# ADC.net
KiCad netlist of a schematic drawn in Altium Designer
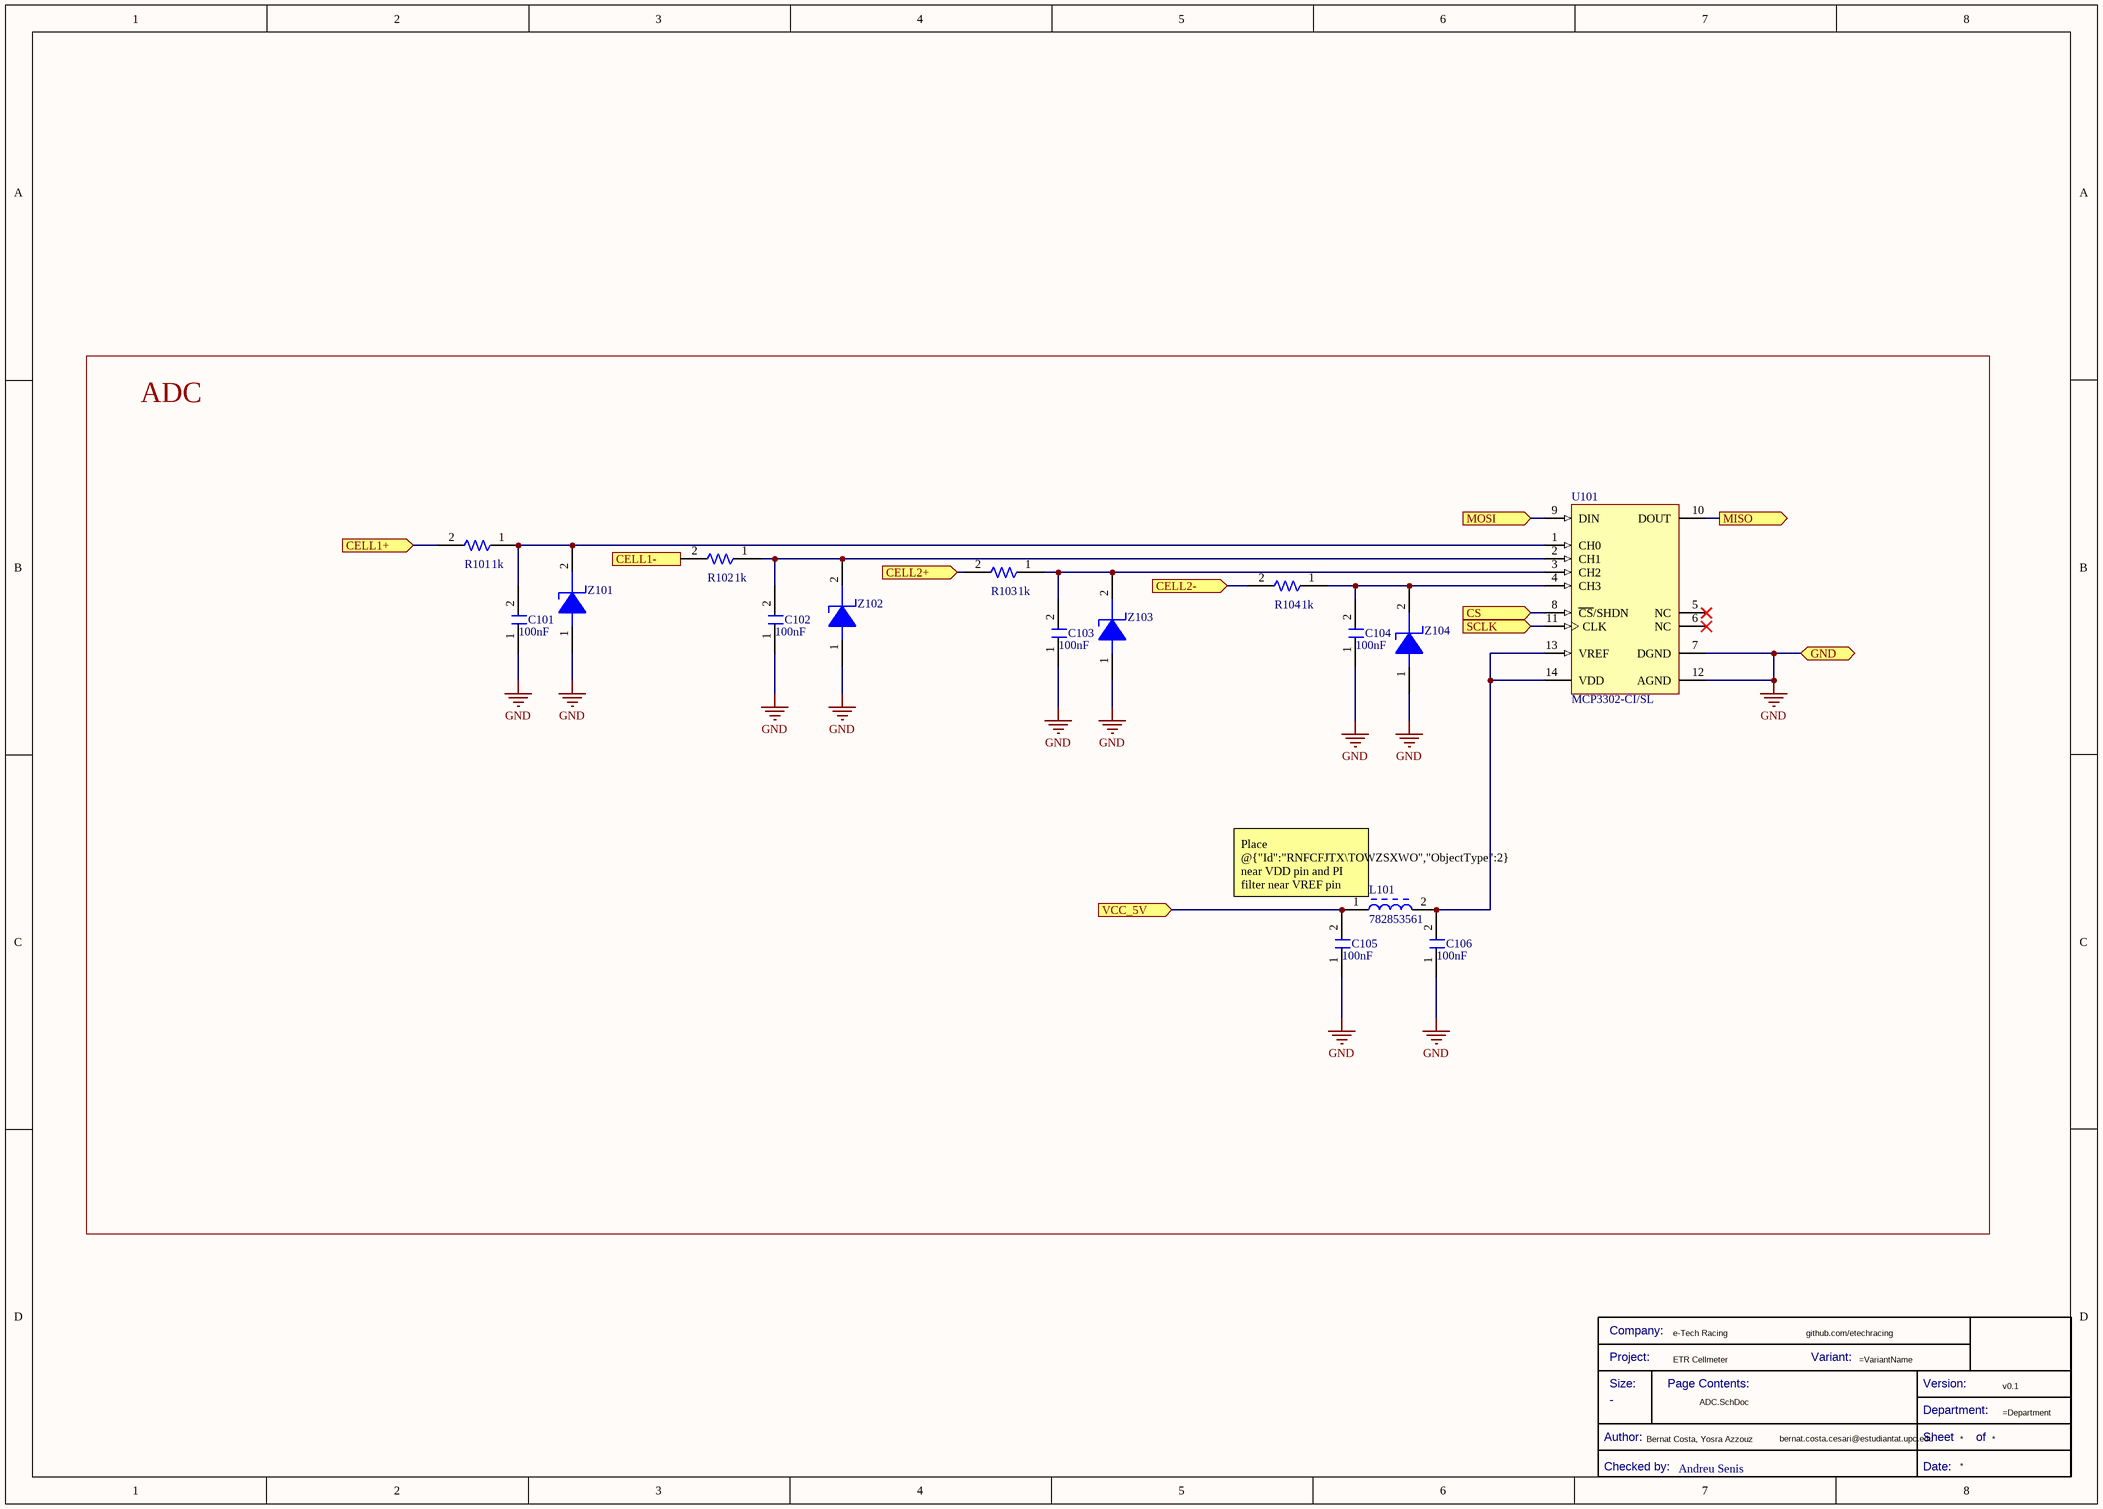
[diagram p0: ADC.SchDoc]

(export (version "E")
  (design (tool "Eeschema 10.0.6"))
  (components
    (comp (ref "C101")
      (value "100nF")
      (footprint "C0805FNPC-R")
      (description "Cap, 0.1ΜF, 50V, 10%, X7R, 0805")
      (fields
        (field (name "TOLERANCE") "10%")
        (field (name "Comment") "C100n-50V-0805FNPC-X7R")
        (field (name ".CREATOR") "DR")
      )
      (libsource (lib "EMEA- E-Tech Racing- I'Escola d'Enginyeria de Barcelona Est") (part "C100p-50V-0805FNPC-C0G/NP0"))
    )
    (comp (ref "C102")
      (value "100nF")
      (footprint "C0805FNPC-R")
      (description "Cap, 0.1ΜF, 50V, 10%, X7R, 0805")
      (fields
        (field (name "TOLERANCE") "10%")
        (field (name "Comment") "C100n-50V-0805FNPC-X7R")
        (field (name ".CREATOR") "DR")
      )
      (libsource (lib "EMEA- E-Tech Racing- I'Escola d'Enginyeria de Barcelona Est") (part "C100p-50V-0805FNPC-C0G/NP0"))
    )
    (comp (ref "C103")
      (value "100nF")
      (footprint "C0805FNPC-R")
      (description "Cap, 0.1ΜF, 50V, 10%, X7R, 0805")
      (fields
        (field (name "TOLERANCE") "10%")
        (field (name "Comment") "C100n-50V-0805FNPC-X7R")
        (field (name ".CREATOR") "DR")
      )
      (libsource (lib "EMEA- E-Tech Racing- I'Escola d'Enginyeria de Barcelona Est") (part "C100p-50V-0805FNPC-C0G/NP0"))
    )
    (comp (ref "C104")
      (value "100nF")
      (footprint "C0805FNPC-R")
      (description "Cap, 0.1ΜF, 50V, 10%, X7R, 0805")
      (fields
        (field (name "TOLERANCE") "10%")
        (field (name "Comment") "C100n-50V-0805FNPC-X7R")
        (field (name ".CREATOR") "DR")
      )
      (libsource (lib "EMEA- E-Tech Racing- I'Escola d'Enginyeria de Barcelona Est") (part "C100p-50V-0805FNPC-C0G/NP0"))
    )
    (comp (ref "C105")
      (value "100nF")
      (footprint "C0805FNPC-R")
      (description "Cap, 0.1ΜF, 50V, 10%, X7R, 0805")
      (fields
        (field (name "TOLERANCE") "10%")
        (field (name "Comment") "C100n-50V-0805FNPC-X7R")
        (field (name ".CREATOR") "DR")
      )
      (libsource (lib "EMEA- E-Tech Racing- I'Escola d'Enginyeria de Barcelona Est") (part "C100p-50V-0805FNPC-C0G/NP0"))
    )
    (comp (ref "C106")
      (value "100nF")
      (footprint "C0805FNPC-R")
      (description "Cap, 0.1ΜF, 50V, 10%, X7R, 0805")
      (fields
        (field (name "TOLERANCE") "10%")
        (field (name "Comment") "C100n-50V-0805FNPC-X7R")
        (field (name ".CREATOR") "DR")
      )
      (libsource (lib "EMEA- E-Tech Racing- I'Escola d'Enginyeria de Barcelona Est") (part "C100p-50V-0805FNPC-C0G/NP0"))
    )
    (comp (ref "L101")
      (value "782853561")
      (footprint "L_Ferrite_bead_0805")
      (fields
        (field (name "TOLERANCE") "25%")
        (field (name "MANUFACTURER PART NUMBER") "BLM18EG331TN1D")
        (field (name "MANUFACTURER") "Murata")
        (field (name ".CREATOR") "GP")
      )
      (libsource (lib "EMEA- E-Tech Racing- I'Escola d'Enginyeria de Barcelona Est") (part "L_Ferrite_bead_782853561"))
    )
    (comp (ref "R101")
      (value "1k")
      (footprint "0805")
      (description "Fixed Resistor, Thin Film, 0.125W, 1000ohm, 150V, 0.1% +/-Tol, 15ppm/Cel, Surface Mount, 0805")
      (fields (field (name "POWER") "125mW") (field (name "TOLERANCE") "0.1%"))
      (libsource (lib "EMEA- E-Tech Racing- I'Escola d'Enginyeria de Barcelona Est") (part "R9.09K-1206FTK"))
    )
    (comp (ref "R102")
      (value "1k")
      (footprint "0805")
      (description "Fixed Resistor, Thin Film, 0.125W, 1000ohm, 150V, 0.1% +/-Tol, 15ppm/Cel, Surface Mount, 0805")
      (fields (field (name "POWER") "125mW") (field (name "TOLERANCE") "0.1%"))
      (libsource (lib "EMEA- E-Tech Racing- I'Escola d'Enginyeria de Barcelona Est") (part "R9.09K-1206FTK"))
    )
    (comp (ref "R103")
      (value "1k")
      (footprint "0805")
      (description "Fixed Resistor, Thin Film, 0.125W, 1000ohm, 150V, 0.1% +/-Tol, 15ppm/Cel, Surface Mount, 0805")
      (fields (field (name "POWER") "125mW") (field (name "TOLERANCE") "0.1%"))
      (libsource (lib "EMEA- E-Tech Racing- I'Escola d'Enginyeria de Barcelona Est") (part "R9.09K-1206FTK"))
    )
    (comp (ref "R104")
      (value "1k")
      (footprint "0805")
      (description "Fixed Resistor, Thin Film, 0.125W, 1000ohm, 150V, 0.1% +/-Tol, 15ppm/Cel, Surface Mount, 0805")
      (fields (field (name "POWER") "125mW") (field (name "TOLERANCE") "0.1%"))
      (libsource (lib "EMEA- E-Tech Racing- I'Escola d'Enginyeria de Barcelona Est") (part "R9.09K-1206FTK"))
    )
    (comp (ref "U101")
      (value "MCP3302-CI/SL")
      (footprint "SOIC-SL14_L")
      (description "ADC, Successive Approximation, 13-Bit, 1 Func, 4 Channel, Serial Access, PDSO14")
      (libsource (lib "EMEA- E-Tech Racing- I'Escola d'Enginyeria de Barcelona Est") (part "CON-ADC-MCP3004-14"))
    )
    (comp (ref "Z101")
      (value "BZD27B5V1P-M3-08")
      (footprint "SODFL370X108-2N")
      (description "Zener Diode, 5.1V V(Z), 2%, 0.8W, Silicon, Unidirectional, DO-219AB")
      (libsource (lib "EMEA- E-Tech Racing- I'Escola d'Enginyeria de Barcelona Est") (part "BZD27B5V1P-M3-08-Symbol-1"))
    )
    (comp (ref "Z102")
      (value "BZD27B5V1P-M3-08")
      (footprint "SODFL370X108-2N")
      (description "Zener Diode, 5.1V V(Z), 2%, 0.8W, Silicon, Unidirectional, DO-219AB")
      (libsource (lib "EMEA- E-Tech Racing- I'Escola d'Enginyeria de Barcelona Est") (part "BZD27B5V1P-M3-08-Symbol-1"))
    )
    (comp (ref "Z103")
      (value "BZD27B5V1P-M3-08")
      (footprint "SODFL370X108-2N")
      (description "Zener Diode, 5.1V V(Z), 2%, 0.8W, Silicon, Unidirectional, DO-219AB")
      (libsource (lib "EMEA- E-Tech Racing- I'Escola d'Enginyeria de Barcelona Est") (part "BZD27B5V1P-M3-08-Symbol-1"))
    )
    (comp (ref "Z104")
      (value "BZD27B5V1P-M3-08")
      (footprint "SODFL370X108-2N")
      (description "Zener Diode, 5.1V V(Z), 2%, 0.8W, Silicon, Unidirectional, DO-219AB")
      (libsource (lib "EMEA- E-Tech Racing- I'Escola d'Enginyeria de Barcelona Est") (part "BZD27B5V1P-M3-08-Symbol-1"))
    )
  )
  (nets
    (net (code "1") (name "/CELL1+") (class "Default")
      (node (ref "R101") (pin "2") (pinfunction "2_2") (pintype "passive"))
    )
    (net (code "2") (name "/CELL1-") (class "Default")
      (node (ref "R102") (pin "2") (pinfunction "2_2") (pintype "passive"))
    )
    (net (code "3") (name "/CELL2+") (class "Default")
      (node (ref "R103") (pin "2") (pinfunction "2_2") (pintype "passive"))
    )
    (net (code "4") (name "/CELL2-") (class "Default")
      (node (ref "R104") (pin "2") (pinfunction "2_2") (pintype "passive"))
    )
    (net (code "5") (name "/CS") (class "Default")
      (node (ref "U101") (pin "8") (pinfunction "~{CS}/SHDN_8") (pintype "input"))
    )
    (net (code "6") (name "/MISO") (class "Default")
      (node (ref "U101") (pin "10") (pinfunction "DOUT_10") (pintype "tri_state"))
    )
    (net (code "7") (name "/MOSI") (class "Default")
      (node (ref "U101") (pin "9") (pinfunction "DIN_9") (pintype "input"))
    )
    (net (code "8") (name "/SCLK") (class "Default")
      (node (ref "U101") (pin "11") (pinfunction "CLK_11") (pintype "input"))
    )
    (net (code "9") (name "/VCC_5V") (class "Default")
      (node (ref "C105") (pin "2") (pinfunction "2_2") (pintype "passive"))
      (node (ref "L101") (pin "1") (pinfunction "1_1") (pintype "passive"))
    )
    (net (code "10") (name "GND") (class "Default")
      (node (ref "C101") (pin "1") (pinfunction "1_1") (pintype "passive"))
      (node (ref "C102") (pin "1") (pinfunction "1_1") (pintype "passive"))
      (node (ref "C103") (pin "1") (pinfunction "1_1") (pintype "passive"))
      (node (ref "C104") (pin "1") (pinfunction "1_1") (pintype "passive"))
      (node (ref "C105") (pin "1") (pinfunction "1_1") (pintype "passive"))
      (node (ref "C106") (pin "1") (pinfunction "1_1") (pintype "passive"))
      (node (ref "U101") (pin "12") (pinfunction "AGND_12") (pintype "power_in"))
      (node (ref "U101") (pin "7") (pinfunction "DGND_7") (pintype "power_in"))
      (node (ref "Z101") (pin "1") (pinfunction "1_1") (pintype "passive"))
      (node (ref "Z102") (pin "1") (pinfunction "1_1") (pintype "passive"))
      (node (ref "Z103") (pin "1") (pinfunction "1_1") (pintype "passive"))
      (node (ref "Z104") (pin "1") (pinfunction "1_1") (pintype "passive"))
    )
    (net (code "11") (name "Net-(U101-CH0)") (class "Default")
      (node (ref "C101") (pin "2") (pinfunction "2_2") (pintype "passive"))
      (node (ref "R101") (pin "1") (pinfunction "1_1") (pintype "passive"))
      (node (ref "U101") (pin "1") (pinfunction "CH0_1") (pintype "input"))
      (node (ref "Z101") (pin "2") (pinfunction "2_2") (pintype "passive"))
    )
    (net (code "12") (name "Net-(U101-CH1)") (class "Default")
      (node (ref "C102") (pin "2") (pinfunction "2_2") (pintype "passive"))
      (node (ref "R102") (pin "1") (pinfunction "1_1") (pintype "passive"))
      (node (ref "U101") (pin "2") (pinfunction "CH1_2") (pintype "input"))
      (node (ref "Z102") (pin "2") (pinfunction "2_2") (pintype "passive"))
    )
    (net (code "13") (name "Net-(U101-CH2)") (class "Default")
      (node (ref "C103") (pin "2") (pinfunction "2_2") (pintype "passive"))
      (node (ref "R103") (pin "1") (pinfunction "1_1") (pintype "passive"))
      (node (ref "U101") (pin "3") (pinfunction "CH2_3") (pintype "input"))
      (node (ref "Z103") (pin "2") (pinfunction "2_2") (pintype "passive"))
    )
    (net (code "14") (name "Net-(U101-CH3)") (class "Default")
      (node (ref "C104") (pin "2") (pinfunction "2_2") (pintype "passive"))
      (node (ref "R104") (pin "1") (pinfunction "1_1") (pintype "passive"))
      (node (ref "U101") (pin "4") (pinfunction "CH3_4") (pintype "input"))
      (node (ref "Z104") (pin "2") (pinfunction "2_2") (pintype "passive"))
    )
    (net (code "15") (name "Net-(U101-VDD)") (class "Default")
      (node (ref "C106") (pin "2") (pinfunction "2_2") (pintype "passive"))
      (node (ref "L101") (pin "2") (pinfunction "2_2") (pintype "passive"))
      (node (ref "U101") (pin "13") (pinfunction "VREF_13") (pintype "input"))
      (node (ref "U101") (pin "14") (pinfunction "VDD_14") (pintype "power_in"))
    )
    (net (code "16") (name "unconnected-(U101-NC-Pad5)") (class "Default")
      (node (ref "U101") (pin "5") (pinfunction "NC_5") (pintype "passive+no_connect"))
    )
    (net (code "17") (name "unconnected-(U101-NC-Pad6)") (class "Default")
      (node (ref "U101") (pin "6") (pinfunction "NC_6") (pintype "passive+no_connect"))
    )
  )
)
